# Detection_Circuit_Sheet_01.net
KiCad netlist of a schematic drawn in Altium Designer
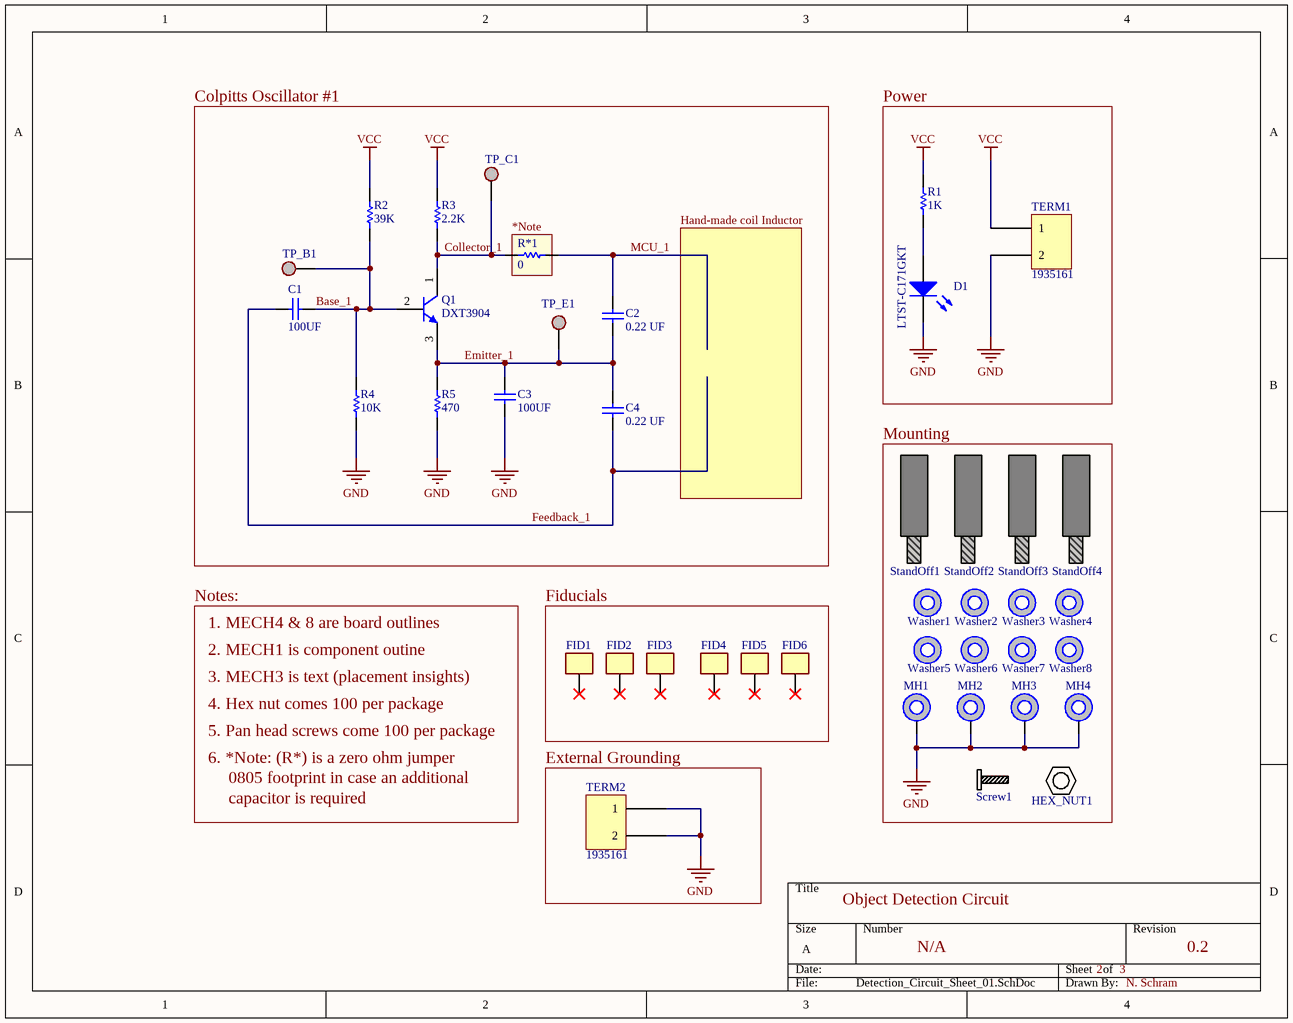
[diagram p0: Detection_Circuit_Sheet_01.SchDoc]

(export (version "E")
  (design (tool "Eeschema 10.0.6"))
  (components
    (comp (ref "C1")
      (value "100UF")
      (footprint "C1210_M")
      (description "CAP CER 100UF 16V X5R 1210")
      (fields (field (name "MANUFACTURER PART NUMBER") "CC1210MKX5R7BB107") (field (name "TOLERANCE") "±20%"))
      (libsource (lib "CC1210MKX5R7BB107") (part "CC1210MKX5R7BB107"))
    )
    (comp (ref "C2")
      (value "08055C224JAT2A")
      (footprint "6-0805_N")
      (description "CAP CER 0.22UF 50V X7R 0805")
      (fields
        (field (name "MANUFACTURER") "AVX Corporation")
        (field (name "TOLERANCE") "±5%")
        (field (name "CAPACITANCE") "0.22 UF")
      )
      (libsource (lib "08055C224JAT2A") (part "08055C224JAT2A"))
    )
    (comp (ref "C3")
      (value "100UF")
      (footprint "C1210_M")
      (description "CAP CER 100UF 16V X5R 1210")
      (fields (field (name "MANUFACTURER PART NUMBER") "CC1210MKX5R7BB107") (field (name "TOLERANCE") "±20%"))
      (libsource (lib "CC1210MKX5R7BB107") (part "CC1210MKX5R7BB107"))
    )
    (comp (ref "C4")
      (value "08055C224JAT2A")
      (footprint "6-0805_N")
      (description "CAP CER 0.22UF 50V X7R 0805")
      (fields
        (field (name "MANUFACTURER") "AVX Corporation")
        (field (name "TOLERANCE") "±5%")
        (field (name "CAPACITANCE") "0.22 UF")
      )
      (libsource (lib "08055C224JAT2A") (part "08055C224JAT2A"))
    )
    (comp (ref "D1")
      (value "LTST-C171GKT")
      (footprint "6-0805_M")
      (description "LED GREEN CLEAR 0805 SMD")
      (fields (field (name "MANUFACTURER") "Vishay Lite-On"))
      (libsource (lib "Miscellaneous Devices") (part "LED3"))
    )
    (comp (ref "FID1")
      (value "Fiducial")
      (footprint "Fiducial")
      (libsource (lib "Fiducial") (part "Fiducial"))
    )
    (comp (ref "FID2")
      (value "Fiducial")
      (footprint "Fiducial")
      (libsource (lib "Fiducial") (part "Fiducial"))
    )
    (comp (ref "FID3")
      (value "Fiducial")
      (footprint "Fiducial")
      (libsource (lib "Fiducial") (part "Fiducial"))
    )
    (comp (ref "FID4")
      (value "Fiducial")
      (footprint "Fiducial")
      (libsource (lib "Fiducial") (part "Fiducial"))
    )
    (comp (ref "FID5")
      (value "Fiducial")
      (footprint "Fiducial")
      (libsource (lib "Fiducial") (part "Fiducial"))
    )
    (comp (ref "FID6")
      (value "Fiducial")
      (footprint "Fiducial")
      (libsource (lib "Fiducial") (part "Fiducial"))
    )
    (comp (ref "HEX_NUT1")
      (value "6-32 Hex Nut")
      (description "HEX NUT 0.245\" STEEL 6-32")
      (fields
        (field (name "MANUFACTURER PART NUMBER") "4701")
        (field (name "MANUFACTURER") "Keystone Electronics")
      )
      (libsource (lib "6-32_Hex_Nut") (part "HEX_NUT"))
    )
    (comp (ref "MH1")
      (value "#6 MH")
      (footprint "#6_MH")
      (description "#6 Mounting Hole")
      (libsource (lib "#6_MH") (part "MH"))
    )
    (comp (ref "MH2")
      (value "#6 MH")
      (footprint "#6_MH")
      (description "#6 Mounting Hole")
      (libsource (lib "#6_MH") (part "MH"))
    )
    (comp (ref "MH3")
      (value "#6 MH")
      (footprint "#6_MH")
      (description "#6 Mounting Hole")
      (libsource (lib "#6_MH") (part "MH"))
    )
    (comp (ref "MH4")
      (value "#6 MH")
      (footprint "#6_MH")
      (description "#6 Mounting Hole")
      (libsource (lib "#6_MH") (part "MH"))
    )
    (comp (ref "Q1")
      (value "DXT3904")
      (footprint "DXT3904-13")
      (description "TRANS NPN 40V 0.2A SOT89-3")
      (fields (field (name "MANUFACTURER PART NUMBER") "DXT3904-13") (field (name "MANUFACTURER") "Diodes"))
      (libsource (lib "DXT3904-13") (part "DXT3904-13"))
    )
    (comp (ref "R*1")
      (value "0")
      (footprint "6-0805_M")
      (description "RES SMD 0 OHM JUMPER 1/8W 0805")
      (fields
        (field (name "MANUFACTURER PART NUMBER") "ERJ-6GEY0R00V")
        (field (name "MANUFACTURER") "Panasonic ECG")
      )
      (libsource (lib "ERJ-6GEY0R00V") (part "ERJ-6GEY0R00V"))
    )
    (comp (ref "R1")
      (value "1K")
      (footprint "6-0805_M")
      (description "RES SMD 1K OHM 1% 1/4W 0805")
      (fields (field (name "MANUFACTURER PART NUMBER") "RNCP0805FTD1K00") (field (name "TOLERANCE") "±1%"))
      (libsource (lib "RNCP0805FTD1K00") (part "RNCP0805FTD1K00"))
    )
    (comp (ref "R2")
      (value "39K")
      (footprint "6-0805_M")
      (description "RES SMD 39K OHM 0.5% 1/4W 0805")
      (fields (field (name "MANUFACTURER PART NUMBER") "ERJ-PB6D3902V") (field (name "TOLERANCE") "±0.5%"))
      (libsource (lib "ERJ-PB6D3902V") (part "ERJ-PB6D3902V"))
    )
    (comp (ref "R3")
      (value "2.2K")
      (footprint "6-0805_M")
      (description "RES SMD 2.2K OHM 0.5% 1/4W 0805")
      (fields (field (name "MANUFACTURER PART NUMBER") "ERJ-PB6D2201V") (field (name "TOLERANCE") "±0.5%"))
      (libsource (lib "ERJ-PB6D2201V") (part "ERJ-PB6D2201V"))
    )
    (comp (ref "R4")
      (value "10K")
      (footprint "6-0805_M")
      (description "RES SMD 10K OHM 1% 1/4W 0805")
      (fields (field (name "MANUFACTURER PART NUMBER") "RNCP0805FTD10K0") (field (name "TOLERANCE") "±1%"))
      (libsource (lib "RNCP0805FTD10K0") (part "RNCP0805FTD10K0"))
    )
    (comp (ref "R5")
      (value "470")
      (footprint "6-0805_M")
      (description "RES SMD 470 OHM 0.5% 1/4W 0805")
      (fields (field (name "MANUFACTURER PART NUMBER") "ERJ-PB6D4700V") (field (name "TOLERANCE") "±0.5%"))
      (libsource (lib "ERJ-PB6D4700V") (part "ERJ-PB6D4700V"))
    )
    (comp (ref "Screw1")
      (value "6-32 Pan Head Screw")
      (description "MACHINE SCREW PAN PHILLIPS 6-32")
      (fields
        (field (name "MANUFACTURER PART NUMBER") "PMSSS6320050PH")
        (field (name "MANUFACTURER") "B&F Fastener")
      )
      (libsource (lib "6-32_Screw") (part "6-32 Screw"))
    )
    (comp (ref "StandOff1")
      (value "6-32 Stand Off")
      (description "HEX STANDOFF 6-32 ALUMINUM 3/4\"")
      (fields
        (field (name "MANUFACTURER PART NUMBER") "8416")
        (field (name "MANUFACTURER") "Keystone Electronics")
      )
      (libsource (lib "6-32_Stand_Off") (part "STANDOFF"))
    )
    (comp (ref "StandOff2")
      (value "6-32 Stand Off")
      (description "HEX STANDOFF 6-32 ALUMINUM 3/4\"")
      (fields
        (field (name "MANUFACTURER PART NUMBER") "8416")
        (field (name "MANUFACTURER") "Keystone Electronics")
      )
      (libsource (lib "6-32_Stand_Off") (part "STANDOFF"))
    )
    (comp (ref "StandOff3")
      (value "6-32 Stand Off")
      (description "HEX STANDOFF 6-32 ALUMINUM 3/4\"")
      (fields
        (field (name "MANUFACTURER PART NUMBER") "8416")
        (field (name "MANUFACTURER") "Keystone Electronics")
      )
      (libsource (lib "6-32_Stand_Off") (part "STANDOFF"))
    )
    (comp (ref "StandOff4")
      (value "6-32 Stand Off")
      (description "HEX STANDOFF 6-32 ALUMINUM 3/4\"")
      (fields
        (field (name "MANUFACTURER PART NUMBER") "8416")
        (field (name "MANUFACTURER") "Keystone Electronics")
      )
      (libsource (lib "6-32_Stand_Off") (part "STANDOFF"))
    )
    (comp (ref "TERM1")
      (value "1935161")
      (footprint "1935161")
      (description "TERM BLOCK PCB 2POS 5.0MM GREEN")
      (fields (field (name "MANUFACTURER") "Phoenix Contact"))
      (libsource (lib "1935161") (part "1935161"))
    )
    (comp (ref "TERM2")
      (value "1935161")
      (footprint "1935161")
      (description "TERM BLOCK PCB 2POS 5.0MM GREEN")
      (fields (field (name "MANUFACTURER") "Phoenix Contact"))
      (libsource (lib "") (part "1935161_1"))
    )
    (comp (ref "TP_B1")
      (value "TestPoint")
      (footprint "TestPoint")
      (description "Test Point")
      (libsource (lib "TestPoint") (part "TestPoint"))
    )
    (comp (ref "TP_C1")
      (value "TestPoint")
      (footprint "TestPoint")
      (description "Test Point")
      (libsource (lib "TestPoint") (part "TestPoint"))
    )
    (comp (ref "TP_E1")
      (value "TestPoint")
      (footprint "TestPoint")
      (description "Test Point")
      (libsource (lib "TestPoint") (part "TestPoint"))
    )
    (comp (ref "Washer1")
      (value "Nylon Washer")
      (description "MACHINE SCREW PAN PHILLIPS 6-32")
      (fields
        (field (name "MANUFACTURER PART NUMBER") "3349")
        (field (name "MANUFACTURER") "Keystone Electronics")
      )
      (libsource (lib "#6_Nylon_Washer") (part "Washer"))
    )
    (comp (ref "Washer2")
      (value "Nylon Washer")
      (description "MACHINE SCREW PAN PHILLIPS 6-32")
      (fields
        (field (name "MANUFACTURER PART NUMBER") "3349")
        (field (name "MANUFACTURER") "Keystone Electronics")
      )
      (libsource (lib "#6_Nylon_Washer") (part "Washer"))
    )
    (comp (ref "Washer3")
      (value "Nylon Washer")
      (description "MACHINE SCREW PAN PHILLIPS 6-32")
      (fields
        (field (name "MANUFACTURER PART NUMBER") "3349")
        (field (name "MANUFACTURER") "Keystone Electronics")
      )
      (libsource (lib "#6_Nylon_Washer") (part "Washer"))
    )
    (comp (ref "Washer4")
      (value "Nylon Washer")
      (description "MACHINE SCREW PAN PHILLIPS 6-32")
      (fields
        (field (name "MANUFACTURER PART NUMBER") "3349")
        (field (name "MANUFACTURER") "Keystone Electronics")
      )
      (libsource (lib "#6_Nylon_Washer") (part "Washer"))
    )
    (comp (ref "Washer5")
      (value "Nylon Washer")
      (description "MACHINE SCREW PAN PHILLIPS 6-32")
      (fields
        (field (name "MANUFACTURER PART NUMBER") "3349")
        (field (name "MANUFACTURER") "Keystone Electronics")
      )
      (libsource (lib "#6_Nylon_Washer") (part "Washer"))
    )
    (comp (ref "Washer6")
      (value "Nylon Washer")
      (description "MACHINE SCREW PAN PHILLIPS 6-32")
      (fields
        (field (name "MANUFACTURER PART NUMBER") "3349")
        (field (name "MANUFACTURER") "Keystone Electronics")
      )
      (libsource (lib "#6_Nylon_Washer") (part "Washer"))
    )
    (comp (ref "Washer7")
      (value "Nylon Washer")
      (description "MACHINE SCREW PAN PHILLIPS 6-32")
      (fields
        (field (name "MANUFACTURER PART NUMBER") "3349")
        (field (name "MANUFACTURER") "Keystone Electronics")
      )
      (libsource (lib "#6_Nylon_Washer") (part "Washer"))
    )
    (comp (ref "Washer8")
      (value "Nylon Washer")
      (description "MACHINE SCREW PAN PHILLIPS 6-32")
      (fields
        (field (name "MANUFACTURER PART NUMBER") "3349")
        (field (name "MANUFACTURER") "Keystone Electronics")
      )
      (libsource (lib "#6_Nylon_Washer") (part "Washer"))
    )
  )
  (nets
    (net (code "1") (name "/Base_1") (class "Default")
      (node (ref "C1") (pin "2") (pinfunction "2_2") (pintype "passive"))
      (node (ref "Q1") (pin "2") (pinfunction "B_2") (pintype "passive"))
      (node (ref "R2") (pin "1") (pinfunction "1_1") (pintype "passive"))
      (node (ref "R4") (pin "2") (pinfunction "2_2") (pintype "passive"))
      (node (ref "TP_B1") (pin "1") (pinfunction "1_1") (pintype "passive"))
    )
    (net (code "2") (name "/Collector_1") (class "Default")
      (node (ref "Q1") (pin "1") (pinfunction "C_1") (pintype "passive"))
      (node (ref "R*1") (pin "1") (pinfunction "1_1") (pintype "passive"))
      (node (ref "R3") (pin "1") (pinfunction "1_1") (pintype "passive"))
      (node (ref "TP_C1") (pin "1") (pinfunction "1_1") (pintype "passive"))
    )
    (net (code "3") (name "/Emitter_1") (class "Default")
      (node (ref "C2") (pin "1") (pinfunction "1_1") (pintype "passive"))
      (node (ref "C3") (pin "2") (pinfunction "2_2") (pintype "passive"))
      (node (ref "C4") (pin "2") (pinfunction "2_2") (pintype "passive"))
      (node (ref "Q1") (pin "3") (pinfunction "E_3") (pintype "passive"))
      (node (ref "R5") (pin "2") (pinfunction "2_2") (pintype "passive"))
      (node (ref "TP_E1") (pin "1") (pinfunction "1_1") (pintype "passive"))
    )
    (net (code "4") (name "/Feedback_1") (class "Default")
      (node (ref "C1") (pin "1") (pinfunction "1_1") (pintype "passive"))
      (node (ref "C4") (pin "1") (pinfunction "1_1") (pintype "passive"))
    )
    (net (code "5") (name "/MCU_1") (class "Default")
      (node (ref "C2") (pin "2") (pinfunction "2_2") (pintype "passive"))
      (node (ref "R*1") (pin "2") (pinfunction "2_2") (pintype "passive"))
    )
    (net (code "6") (name "GND") (class "Default")
      (node (ref "C3") (pin "1") (pinfunction "1_1") (pintype "passive"))
      (node (ref "D1") (pin "2") (pinfunction "K_2") (pintype "passive"))
      (node (ref "MH1") (pin "MH") (pinfunction "MH_MH") (pintype "passive"))
      (node (ref "MH2") (pin "MH") (pinfunction "MH_MH") (pintype "passive"))
      (node (ref "MH3") (pin "MH") (pinfunction "MH_MH") (pintype "passive"))
      (node (ref "MH4") (pin "MH") (pinfunction "MH_MH") (pintype "passive"))
      (node (ref "R4") (pin "1") (pinfunction "1_1") (pintype "passive"))
      (node (ref "R5") (pin "1") (pinfunction "1_1") (pintype "passive"))
      (node (ref "TERM1") (pin "2") (pinfunction "2_2") (pintype "passive"))
      (node (ref "TERM2") (pin "1") (pinfunction "1_1") (pintype "passive"))
      (node (ref "TERM2") (pin "2") (pinfunction "2_2") (pintype "passive"))
    )
    (net (code "7") (name "Net-(D1-A)") (class "Default")
      (node (ref "D1") (pin "1") (pinfunction "A_1") (pintype "passive"))
      (node (ref "R1") (pin "1") (pinfunction "1_1") (pintype "passive"))
    )
    (net (code "8") (name "VCC") (class "Default")
      (node (ref "R1") (pin "2") (pinfunction "2_2") (pintype "passive"))
      (node (ref "R2") (pin "2") (pinfunction "2_2") (pintype "passive"))
      (node (ref "R3") (pin "2") (pinfunction "2_2") (pintype "passive"))
      (node (ref "TERM1") (pin "1") (pinfunction "1_1") (pintype "passive"))
    )
    (net (code "9") (name "unconnected-(FID1-PadFID)") (class "Default")
      (node (ref "FID1") (pin "FID") (pinfunction "FID_FID") (pintype "passive+no_connect"))
    )
    (net (code "10") (name "unconnected-(FID2-PadFID)") (class "Default")
      (node (ref "FID2") (pin "FID") (pinfunction "FID_FID") (pintype "passive+no_connect"))
    )
    (net (code "11") (name "unconnected-(FID3-PadFID)") (class "Default")
      (node (ref "FID3") (pin "FID") (pinfunction "FID_FID") (pintype "passive+no_connect"))
    )
    (net (code "12") (name "unconnected-(FID4-PadFID)") (class "Default")
      (node (ref "FID4") (pin "FID") (pinfunction "FID_FID") (pintype "passive+no_connect"))
    )
    (net (code "13") (name "unconnected-(FID5-PadFID)") (class "Default")
      (node (ref "FID5") (pin "FID") (pinfunction "FID_FID") (pintype "passive+no_connect"))
    )
    (net (code "14") (name "unconnected-(FID6-PadFID)") (class "Default")
      (node (ref "FID6") (pin "FID") (pinfunction "FID_FID") (pintype "passive+no_connect"))
    )
  )
)
